# HC-SR04_Shield.net
KiCad netlist of a schematic drawn in EAGLE
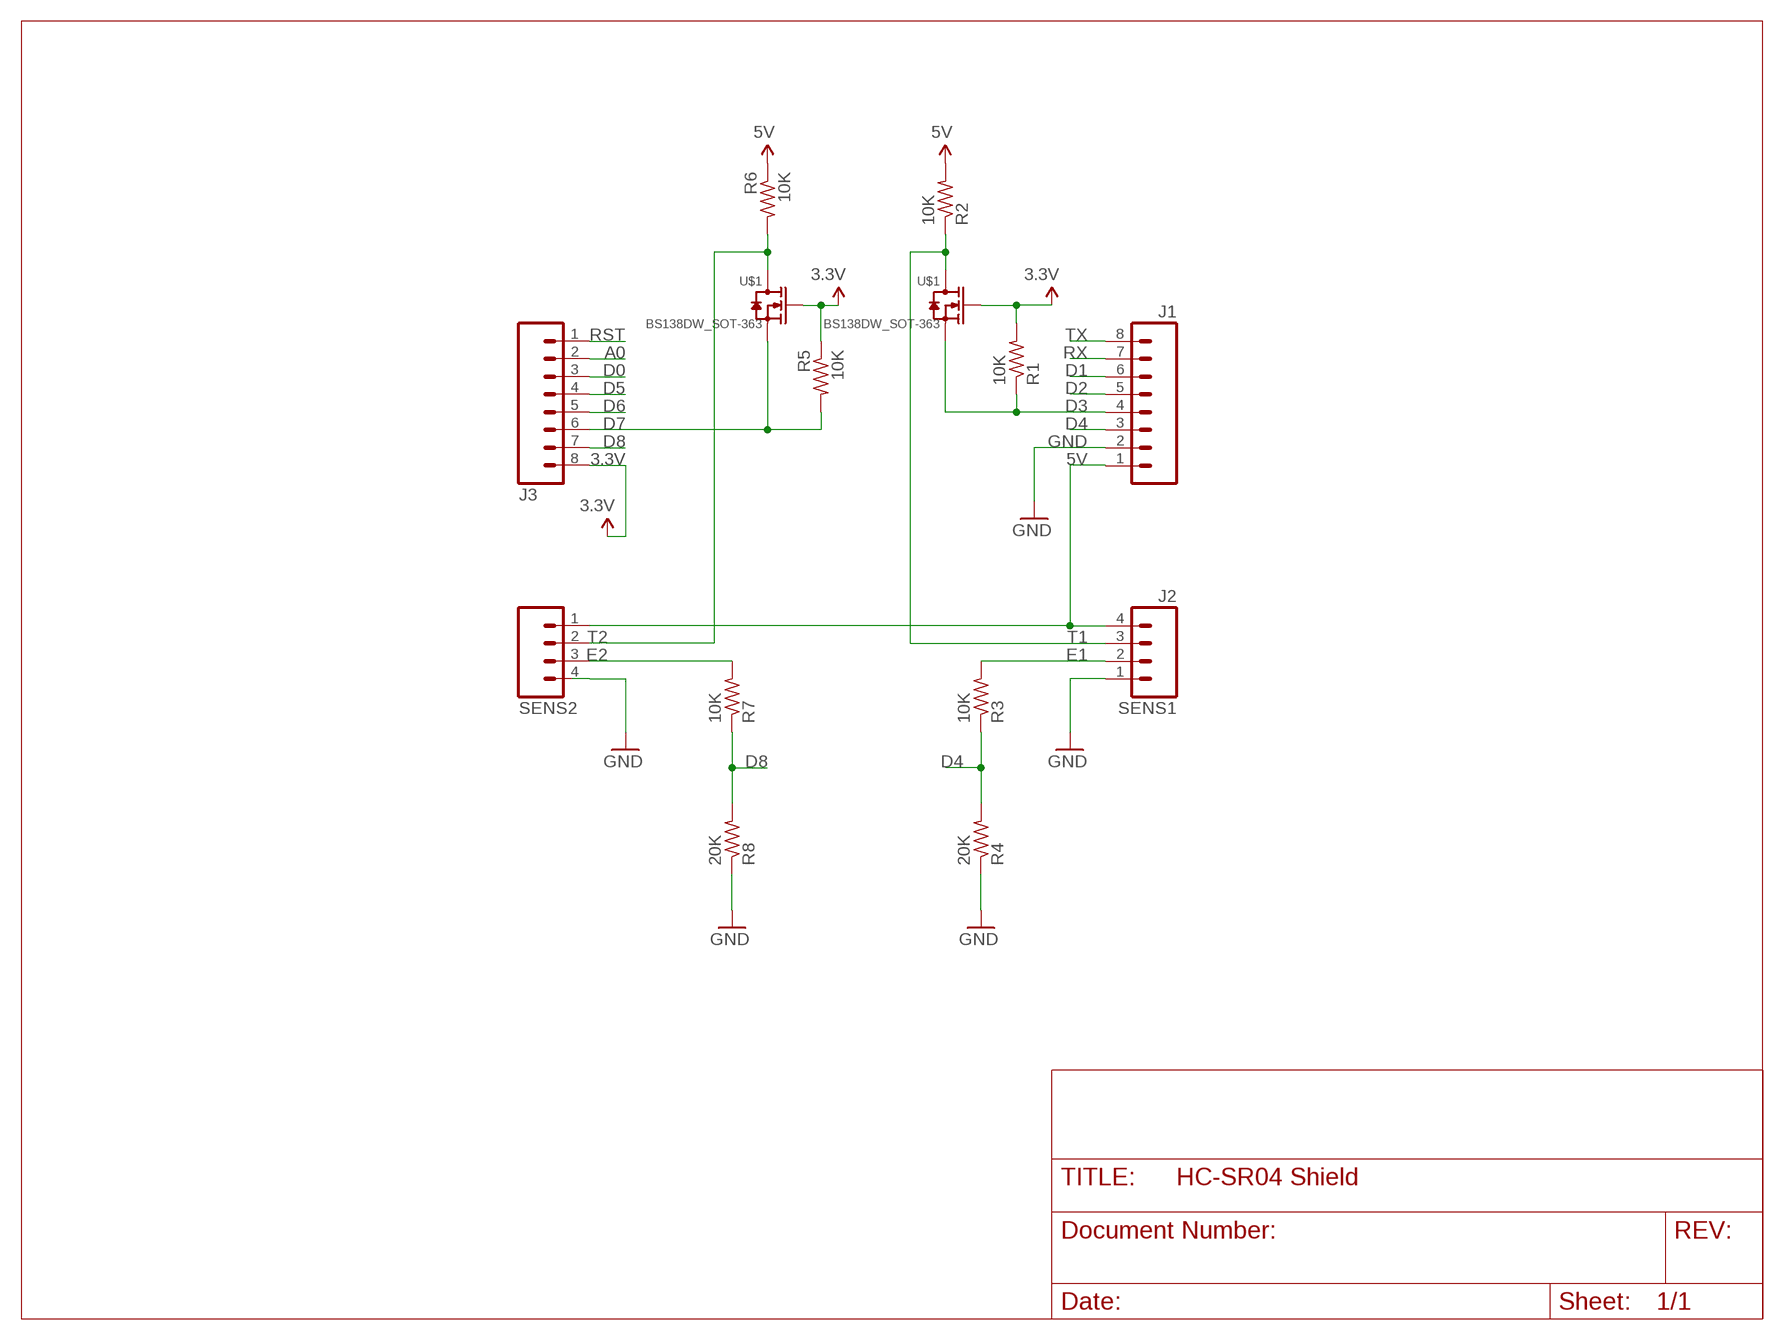
[diagram p0: schematic, sheet 1]

(export (version "E")
  (design (tool "Eeschema 10.0.6"))
  (components
    (comp (ref "J1")
      (value "M08SILK_FEMALE_PTH")
      (footprint "eagle-import:1X08")
      (libsource (lib "eagle-import") (part "M08SILK_FEMALE_PTH"))
    )
    (comp (ref "J2")
      (value "SENS1")
      (footprint "eagle-import:1X04")
      (libsource (lib "eagle-import") (part "M04PTH"))
    )
    (comp (ref "J3")
      (value "M08SILK_FEMALE_PTH")
      (footprint "eagle-import:1X08")
      (libsource (lib "eagle-import") (part "M08SILK_FEMALE_PTH"))
    )
    (comp (ref "R1")
      (value "10K")
      (footprint "eagle-import:R0805")
      (libsource (lib "eagle-import") (part "R-US_R0805"))
    )
    (comp (ref "R2")
      (value "10K")
      (footprint "eagle-import:R0805")
      (libsource (lib "eagle-import") (part "R-US_R0805"))
    )
    (comp (ref "R3")
      (value "10K")
      (footprint "eagle-import:R0805")
      (libsource (lib "eagle-import") (part "R-US_R0805"))
    )
    (comp (ref "R4")
      (value "20K")
      (footprint "eagle-import:R0805")
      (libsource (lib "eagle-import") (part "R-US_R0805"))
    )
    (comp (ref "R5")
      (value "10K")
      (footprint "eagle-import:R0805")
      (libsource (lib "eagle-import") (part "R-US_R0805"))
    )
    (comp (ref "R6")
      (value "10K")
      (footprint "eagle-import:R0805")
      (libsource (lib "eagle-import") (part "R-US_R0805"))
    )
    (comp (ref "R7")
      (value "10K")
      (footprint "eagle-import:R0805")
      (libsource (lib "eagle-import") (part "R-US_R0805"))
    )
    (comp (ref "R8")
      (value "20K")
      (footprint "eagle-import:R0805")
      (libsource (lib "eagle-import") (part "R-US_R0805"))
    )
    (comp (ref "SENS2")
      (value "M04JST-PTH-VERT")
      (footprint "eagle-import:JST-4-PTH-VERT")
      (libsource (lib "eagle-import") (part "M04JST-PTH-VERT"))
    )
    (comp (ref "U$1")
      (value "BS138DW_SOT-363")
      (footprint "eagle-import:SOT363")
      (libsource (lib "eagle-import") (part "BS138DW_SOT-363"))
    )
  )
  (nets
    (net (code "1") (name "/A0") (class "Default")
      (node (ref "J3") (pin "2") (pinfunction "2_2") (pintype "passive"))
    )
    (net (code "2") (name "/D0") (class "Default")
      (node (ref "J3") (pin "3") (pinfunction "3_3") (pintype "passive"))
    )
    (net (code "3") (name "/D1") (class "Default")
      (node (ref "J1") (pin "6") (pinfunction "6_6") (pintype "passive"))
    )
    (net (code "4") (name "/D2") (class "Default")
      (node (ref "J1") (pin "5") (pinfunction "5_5") (pintype "passive"))
    )
    (net (code "5") (name "/D3") (class "Default")
      (node (ref "J1") (pin "4") (pinfunction "4_4") (pintype "passive"))
      (node (ref "R1") (pin "1") (pinfunction "1_1") (pintype "passive"))
      (node (ref "U$1") (pin "4") (pinfunction "S_4") (pintype "passive"))
    )
    (net (code "6") (name "/D4") (class "Default")
      (node (ref "J1") (pin "3") (pinfunction "3_3") (pintype "passive"))
      (node (ref "R3") (pin "1") (pinfunction "1_1") (pintype "passive"))
      (node (ref "R4") (pin "2") (pinfunction "2_2") (pintype "passive"))
    )
    (net (code "7") (name "/D5") (class "Default")
      (node (ref "J3") (pin "4") (pinfunction "4_4") (pintype "passive"))
    )
    (net (code "8") (name "/D6") (class "Default")
      (node (ref "J3") (pin "5") (pinfunction "5_5") (pintype "passive"))
    )
    (net (code "9") (name "/D7") (class "Default")
      (node (ref "J3") (pin "6") (pinfunction "6_6") (pintype "passive"))
      (node (ref "R5") (pin "2") (pinfunction "2_2") (pintype "passive"))
      (node (ref "U$1") (pin "1") (pinfunction "S1_1") (pintype "passive"))
    )
    (net (code "10") (name "/D8") (class "Default")
      (node (ref "J3") (pin "7") (pinfunction "7_7") (pintype "passive"))
      (node (ref "R7") (pin "1") (pinfunction "1_1") (pintype "passive"))
      (node (ref "R8") (pin "2") (pinfunction "2_2") (pintype "passive"))
    )
    (net (code "11") (name "/E1") (class "Default")
      (node (ref "J2") (pin "2") (pinfunction "2_2") (pintype "passive"))
      (node (ref "R3") (pin "2") (pinfunction "2_2") (pintype "passive"))
    )
    (net (code "12") (name "/E2") (class "Default")
      (node (ref "R7") (pin "2") (pinfunction "2_2") (pintype "passive"))
      (node (ref "SENS2") (pin "3") (pinfunction "3_3") (pintype "passive"))
    )
    (net (code "13") (name "/RST") (class "Default")
      (node (ref "J3") (pin "1") (pinfunction "1_1") (pintype "passive"))
    )
    (net (code "14") (name "/RX") (class "Default")
      (node (ref "J1") (pin "7") (pinfunction "7_7") (pintype "passive"))
    )
    (net (code "15") (name "/T1") (class "Default")
      (node (ref "J2") (pin "3") (pinfunction "3_3") (pintype "passive"))
      (node (ref "R2") (pin "1") (pinfunction "1_1") (pintype "passive"))
      (node (ref "U$1") (pin "3") (pinfunction "D_3") (pintype "passive"))
    )
    (net (code "16") (name "/T2") (class "Default")
      (node (ref "R6") (pin "2") (pinfunction "2_2") (pintype "passive"))
      (node (ref "SENS2") (pin "2") (pinfunction "2_2") (pintype "passive"))
      (node (ref "U$1") (pin "6") (pinfunction "D1_6") (pintype "passive"))
    )
    (net (code "17") (name "/TX") (class "Default")
      (node (ref "J1") (pin "8") (pinfunction "8_8") (pintype "passive"))
    )
    (net (code "18") (name "3.3V") (class "Default")
      (node (ref "J3") (pin "8") (pinfunction "8_8") (pintype "passive"))
      (node (ref "R1") (pin "2") (pinfunction "2_2") (pintype "passive"))
      (node (ref "R5") (pin "1") (pinfunction "1_1") (pintype "passive"))
      (node (ref "U$1") (pin "2") (pinfunction "G1_2") (pintype "passive"))
      (node (ref "U$1") (pin "5") (pinfunction "G_5") (pintype "passive"))
    )
    (net (code "19") (name "5V") (class "Default")
      (node (ref "J1") (pin "1") (pinfunction "1_1") (pintype "passive"))
      (node (ref "J2") (pin "4") (pinfunction "4_4") (pintype "passive"))
      (node (ref "R2") (pin "2") (pinfunction "2_2") (pintype "passive"))
      (node (ref "R6") (pin "1") (pinfunction "1_1") (pintype "passive"))
      (node (ref "SENS2") (pin "1") (pinfunction "1_1") (pintype "passive"))
    )
    (net (code "20") (name "GND") (class "Default")
      (node (ref "J1") (pin "2") (pinfunction "2_2") (pintype "passive"))
      (node (ref "J2") (pin "1") (pinfunction "1_1") (pintype "passive"))
      (node (ref "R4") (pin "1") (pinfunction "1_1") (pintype "passive"))
      (node (ref "R8") (pin "1") (pinfunction "1_1") (pintype "passive"))
      (node (ref "SENS2") (pin "4") (pinfunction "4_4") (pintype "passive"))
    )
  )
)
